# Sheet_1.net
KiCad netlist of a schematic drawn in EasyEDA
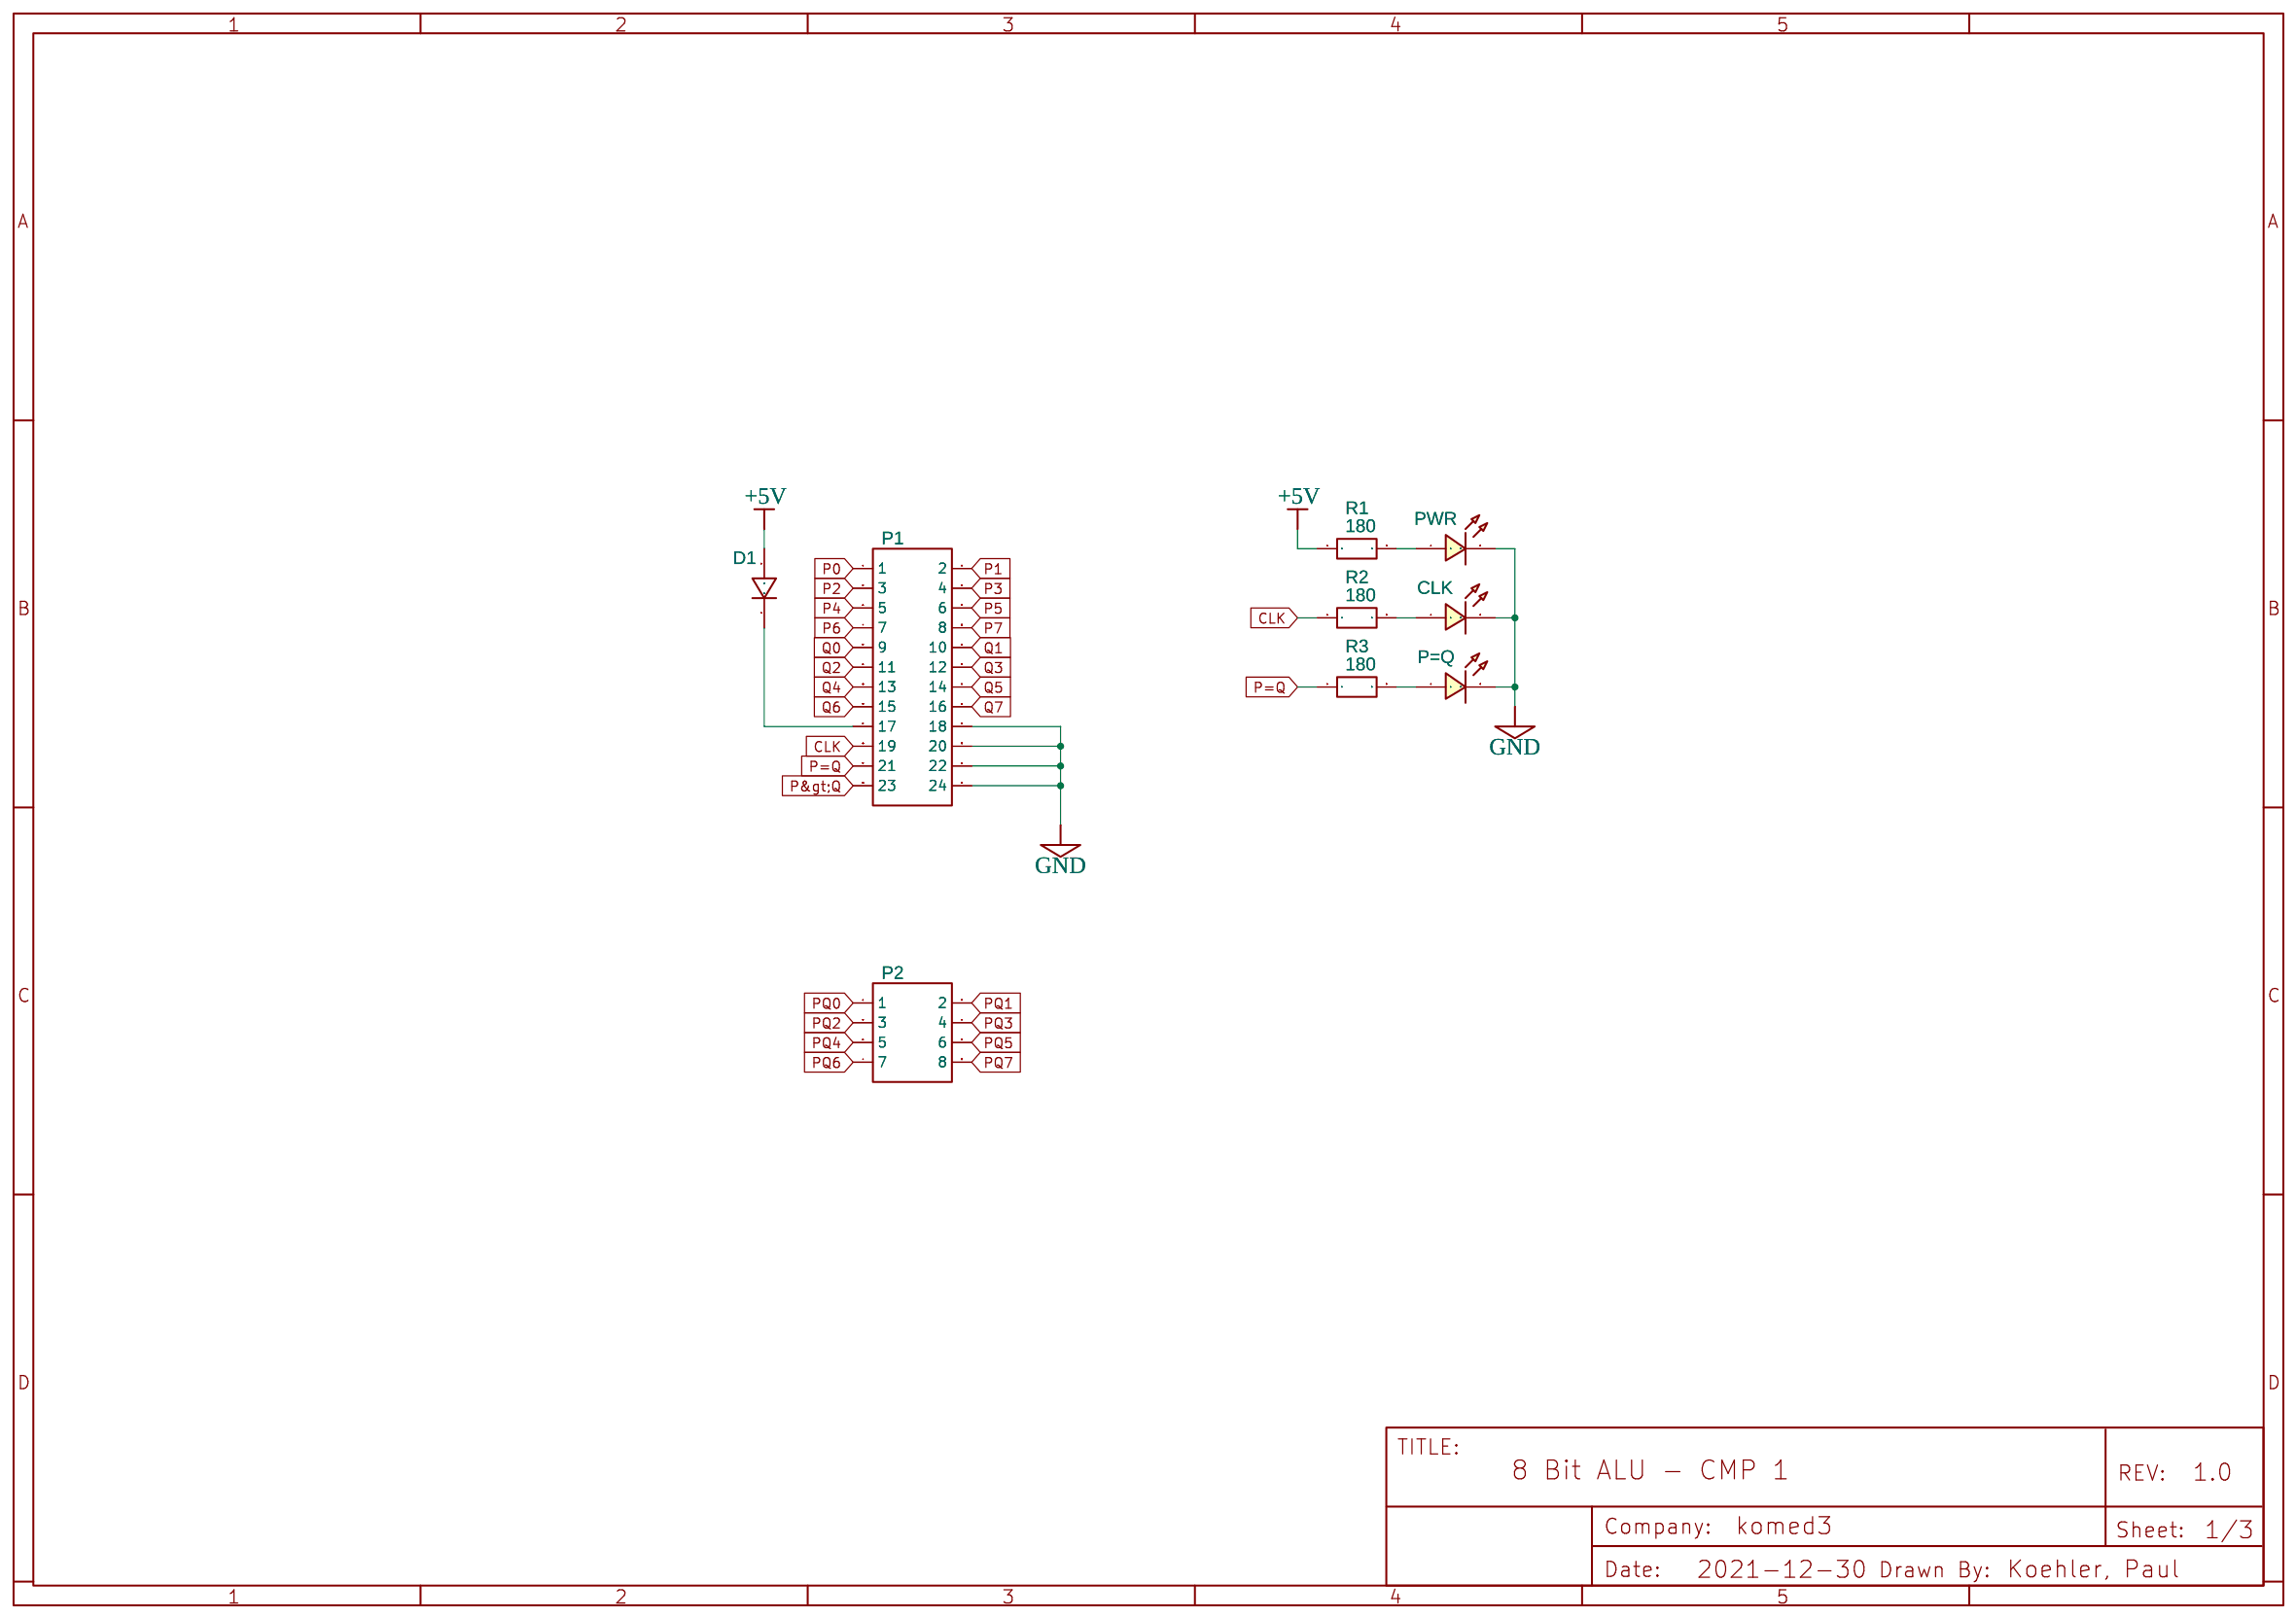
[diagram p0: schematic sheet]

(export (version "E")
  (design (tool "Eeschema 10.0.6"))
  (components
    (comp (ref "CLK")
      (value "LED-TH-5mm_R")
      (fields
        (field (name "BOM_Manufacturer Part") "333-2SURD/S530-A3")
        (field (name "BOM_Supplier Part") "C87271")
      )
      (libsource (lib "") (part "LED-TH-5mm_R_2"))
    )
    (comp (ref "D1")
      (value "1N4007")
      (fields (field (name "BOM_Supplier Part") "C106903"))
      (libsource (lib "") (part "1N4007"))
    )
    (comp (ref "P1")
      (value "HDR-IDC-2.54-2X12P")
      (fields
        (field (name "BOM_Manufacturer Part") "IDC Box 2X12 2.54MM")
        (field (name "BOM_Supplier Part") "C9137")
      )
      (libsource (lib "") (part "HDR-IDC-2.54-2X12P"))
    )
    (comp (ref "P2")
      (value "HDR-IDC-2.54-2X4P")
      (fields
        (field (name "BOM_Manufacturer Part") "IDC Box 2X4 2.54MM")
        (field (name "BOM_Supplier Part") "C9135")
      )
      (libsource (lib "") (part "HDR-IDC-2.54-2X4P"))
    )
    (comp (ref "P=Q")
      (value "LED-TH-5mm_R")
      (fields
        (field (name "BOM_Manufacturer Part") "333-2SURD/S530-A3")
        (field (name "BOM_Supplier Part") "C87271")
      )
      (libsource (lib "") (part "LED-TH-5mm_R_1"))
    )
    (comp (ref "PWR")
      (value "LED-TH-5mm_R")
      (fields
        (field (name "BOM_Manufacturer Part") "333-2SURD/S530-A3")
        (field (name "BOM_Supplier Part") "C87271")
      )
      (libsource (lib "") (part "LED-TH-5mm_R"))
    )
    (comp (ref "R1") (value "180") (libsource (lib "") (part "R_AXIAL-0.3_EU")))
    (comp (ref "R2") (value "180") (libsource (lib "") (part "R_AXIAL-0.3_EU")))
    (comp (ref "R3") (value "180") (libsource (lib "") (part "R_AXIAL-0.3_EU")))
  )
  (nets
    (net (code "1") (name "+5V") (class "Default")
      (node (ref "D1") (pin "2") (pinfunction "2_2") (pintype "unspecified"))
      (node (ref "R1") (pin "1") (pinfunction "1_1") (pintype "unspecified"))
    )
    (net (code "2") (name "CLK") (class "Default")
      (node (ref "P1") (pin "19") (pinfunction "19_19") (pintype "unspecified"))
      (node (ref "R2") (pin "1") (pinfunction "1_1") (pintype "unspecified"))
    )
    (net (code "3") (name "GND") (class "Default")
      (node (ref "CLK") (pin "2") (pinfunction "2_2") (pintype "unspecified"))
      (node (ref "P1") (pin "18") (pinfunction "18_18") (pintype "unspecified"))
      (node (ref "P1") (pin "20") (pinfunction "20_20") (pintype "unspecified"))
      (node (ref "P1") (pin "22") (pinfunction "22_22") (pintype "unspecified"))
      (node (ref "P1") (pin "24") (pinfunction "24_24") (pintype "unspecified"))
      (node (ref "P=Q") (pin "2") (pinfunction "2_2") (pintype "unspecified"))
      (node (ref "PWR") (pin "2") (pinfunction "2_2") (pintype "unspecified"))
    )
    (net (code "4") (name "Net-(CLK-Pad1)") (class "Default")
      (node (ref "CLK") (pin "1") (pinfunction "1_1") (pintype "unspecified"))
      (node (ref "R2") (pin "2") (pinfunction "2_2") (pintype "unspecified"))
    )
    (net (code "5") (name "Net-(D1-Pad1)") (class "Default")
      (node (ref "D1") (pin "1") (pinfunction "1_1") (pintype "unspecified"))
      (node (ref "P1") (pin "17") (pinfunction "17_17") (pintype "unspecified"))
    )
    (net (code "6") (name "Net-(P=Q-Pad1)") (class "Default")
      (node (ref "P=Q") (pin "1") (pinfunction "1_1") (pintype "unspecified"))
      (node (ref "R3") (pin "2") (pinfunction "2_2") (pintype "unspecified"))
    )
    (net (code "7") (name "Net-(PWR-Pad1)") (class "Default")
      (node (ref "PWR") (pin "1") (pinfunction "1_1") (pintype "unspecified"))
      (node (ref "R1") (pin "2") (pinfunction "2_2") (pintype "unspecified"))
    )
    (net (code "8") (name "P&gt;Q") (class "Default")
      (node (ref "P1") (pin "23") (pinfunction "23_23") (pintype "unspecified"))
    )
    (net (code "9") (name "P0") (class "Default")
      (node (ref "P1") (pin "1") (pinfunction "1_1") (pintype "unspecified"))
    )
    (net (code "10") (name "P1") (class "Default")
      (node (ref "P1") (pin "2") (pinfunction "2_2") (pintype "unspecified"))
    )
    (net (code "11") (name "P2") (class "Default")
      (node (ref "P1") (pin "3") (pinfunction "3_3") (pintype "unspecified"))
    )
    (net (code "12") (name "P3") (class "Default")
      (node (ref "P1") (pin "4") (pinfunction "4_4") (pintype "unspecified"))
    )
    (net (code "13") (name "P4") (class "Default")
      (node (ref "P1") (pin "5") (pinfunction "5_5") (pintype "unspecified"))
    )
    (net (code "14") (name "P5") (class "Default")
      (node (ref "P1") (pin "6") (pinfunction "6_6") (pintype "unspecified"))
    )
    (net (code "15") (name "P6") (class "Default")
      (node (ref "P1") (pin "7") (pinfunction "7_7") (pintype "unspecified"))
    )
    (net (code "16") (name "P7") (class "Default")
      (node (ref "P1") (pin "8") (pinfunction "8_8") (pintype "unspecified"))
    )
    (net (code "17") (name "P=Q") (class "Default")
      (node (ref "P1") (pin "21") (pinfunction "21_21") (pintype "unspecified"))
      (node (ref "R3") (pin "1") (pinfunction "1_1") (pintype "unspecified"))
    )
    (net (code "18") (name "PQ0") (class "Default")
      (node (ref "P2") (pin "1") (pinfunction "1_1") (pintype "unspecified"))
    )
    (net (code "19") (name "PQ1") (class "Default")
      (node (ref "P2") (pin "2") (pinfunction "2_2") (pintype "unspecified"))
    )
    (net (code "20") (name "PQ2") (class "Default")
      (node (ref "P2") (pin "3") (pinfunction "3_3") (pintype "unspecified"))
    )
    (net (code "21") (name "PQ3") (class "Default")
      (node (ref "P2") (pin "4") (pinfunction "4_4") (pintype "unspecified"))
    )
    (net (code "22") (name "PQ4") (class "Default")
      (node (ref "P2") (pin "5") (pinfunction "5_5") (pintype "unspecified"))
    )
    (net (code "23") (name "PQ5") (class "Default")
      (node (ref "P2") (pin "6") (pinfunction "6_6") (pintype "unspecified"))
    )
    (net (code "24") (name "PQ6") (class "Default")
      (node (ref "P2") (pin "7") (pinfunction "7_7") (pintype "unspecified"))
    )
    (net (code "25") (name "PQ7") (class "Default")
      (node (ref "P2") (pin "8") (pinfunction "8_8") (pintype "unspecified"))
    )
    (net (code "26") (name "Q0") (class "Default")
      (node (ref "P1") (pin "9") (pinfunction "9_9") (pintype "unspecified"))
    )
    (net (code "27") (name "Q1") (class "Default")
      (node (ref "P1") (pin "10") (pinfunction "10_10") (pintype "unspecified"))
    )
    (net (code "28") (name "Q2") (class "Default")
      (node (ref "P1") (pin "11") (pinfunction "11_11") (pintype "unspecified"))
    )
    (net (code "29") (name "Q3") (class "Default")
      (node (ref "P1") (pin "12") (pinfunction "12_12") (pintype "unspecified"))
    )
    (net (code "30") (name "Q4") (class "Default")
      (node (ref "P1") (pin "13") (pinfunction "13_13") (pintype "unspecified"))
    )
    (net (code "31") (name "Q5") (class "Default")
      (node (ref "P1") (pin "14") (pinfunction "14_14") (pintype "unspecified"))
    )
    (net (code "32") (name "Q6") (class "Default")
      (node (ref "P1") (pin "15") (pinfunction "15_15") (pintype "unspecified"))
    )
    (net (code "33") (name "Q7") (class "Default")
      (node (ref "P1") (pin "16") (pinfunction "16_16") (pintype "unspecified"))
    )
  )
)
